# stable_grid_optocoupler.net
KiCad netlist of a schematic drawn in EAGLE
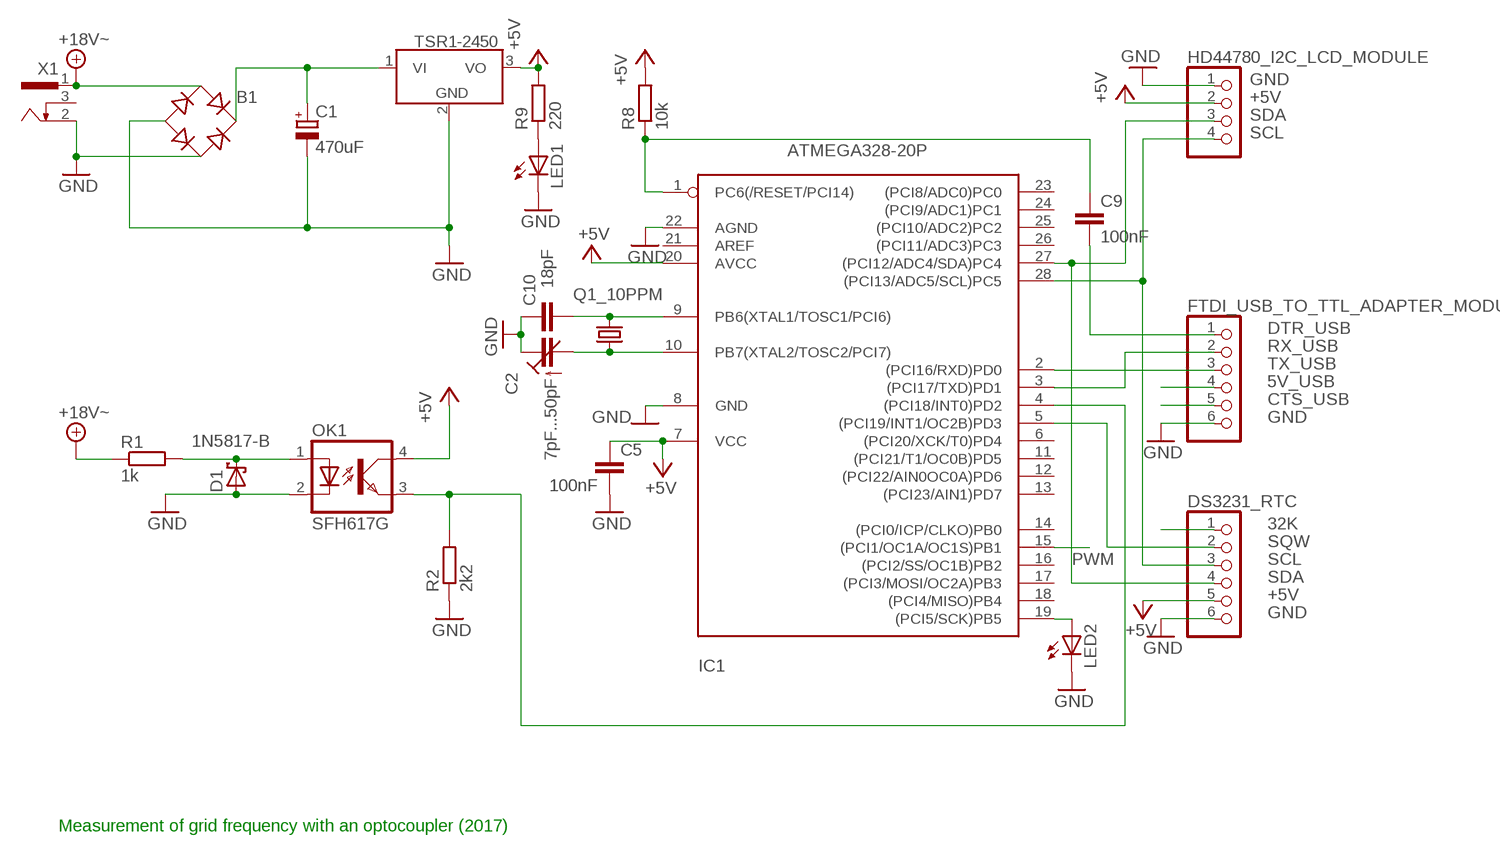
[diagram p0: schematic, sheet 1]

(export (version "E")
  (design (tool "Eeschema 10.0.6"))
  (components
    (comp (ref "B1")
      (value "B-DIL")
      (footprint "eagle-import:B-DIL")
      (libsource (lib "eagle-import") (part "B-DIL"))
    )
    (comp (ref "C1")
      (value "470uF")
      (footprint "eagle-import:085CS_1AR")
      (libsource (lib "eagle-import") (part "CPOL-EU085CS-1AR"))
    )
    (comp (ref "C2")
      (value "7pF...50pF")
      (footprint "eagle-import:CTRIM808-BC")
      (libsource (lib "eagle-import") (part "C-TRIMM808"))
    )
    (comp (ref "C5")
      (value "100nF")
      (footprint "eagle-import:C025-024X044")
      (libsource (lib "eagle-import") (part "C-EU025-024X044"))
    )
    (comp (ref "C9")
      (value "100nF")
      (footprint "eagle-import:C025-024X044")
      (libsource (lib "eagle-import") (part "C-EU025-024X044"))
    )
    (comp (ref "C10")
      (value "18pF")
      (footprint "eagle-import:C025-024X044")
      (libsource (lib "eagle-import") (part "C-EU025-024X044"))
    )
    (comp (ref "D1")
      (value "1N5817-B")
      (footprint "eagle-import:DO41-7.6")
      (libsource (lib "eagle-import") (part "1N5817-B"))
    )
    (comp (ref "DS3231_RTC")
      (value "PINHD-1X6")
      (footprint "eagle-import:1X06")
      (libsource (lib "eagle-import") (part "PINHD-1X6"))
    )
    (comp (ref "FTDI_USB_TO_TTL_ADAPTER_MODULE")
      (value "PINHD-1X6")
      (footprint "eagle-import:1X06")
      (libsource (lib "eagle-import") (part "PINHD-1X6"))
    )
    (comp (ref "HD44780_I2C_LCD_MODULE")
      (value "PINHD-1X4")
      (footprint "eagle-import:1X04")
      (libsource (lib "eagle-import") (part "PINHD-1X4"))
    )
    (comp (ref "IC1")
      (value "ATMEGA328-20P")
      (footprint "eagle-import:DIL28-3")
      (libsource (lib "eagle-import") (part "ATMEGA328P-20"))
    )
    (comp (ref "LED1")
      (value "LAP4-BOTTOM")
      (footprint "eagle-import:P47F-BOTTOM")
      (libsource (lib "eagle-import") (part "P4-BOTTOMLA"))
    )
    (comp (ref "LED2")
      (value "LYP4-BOTTOM")
      (footprint "eagle-import:P47F-BOTTOM")
      (libsource (lib "eagle-import") (part "P4-BOTTOMLY"))
    )
    (comp (ref "OK1")
      (value "SFH617G")
      (footprint "eagle-import:DIL04B")
      (fields (field (name "MF") "VISHAY/TELEFUNKEN") (field (name "MPN") "SFH617A-3"))
      (libsource (lib "eagle-import") (part "SFH617G"))
    )
    (comp (ref "Q1_10PPM")
      (value "CRYSTALHC49S")
      (footprint "eagle-import:HC49_S")
      (libsource (lib "eagle-import") (part "CRYSTALHC49S"))
    )
    (comp (ref "R1")
      (value "1k")
      (footprint "eagle-import:M0805")
      (libsource (lib "eagle-import") (part "R-EU_M0805"))
    )
    (comp (ref "R2")
      (value "2k2")
      (footprint "eagle-import:M0805")
      (libsource (lib "eagle-import") (part "R-EU_M0805"))
    )
    (comp (ref "R8")
      (value "10k")
      (footprint "eagle-import:M0805")
      (libsource (lib "eagle-import") (part "R-EU_M0805"))
    )
    (comp (ref "R9")
      (value "220")
      (footprint "eagle-import:M0805")
      (libsource (lib "eagle-import") (part "R-EU_M0805"))
    )
    (comp (ref "TSR1-2450")
      (value "TSR_1-24_")
      (footprint "eagle-import:TSR-1")
      (libsource (lib "eagle-import") (part "TSR_1-24_"))
    )
    (comp (ref "X1")
      (value "9V")
      (footprint "eagle-import:733980-62")
      (libsource (lib "eagle-import") (part "73398?0-62"))
    )
  )
  (nets
    (net (code "1") (name "+5V") (class "Default")
      (node (ref "C5") (pin "1") (pinfunction "1_1") (pintype "passive"))
      (node (ref "DS3231_RTC") (pin "5") (pinfunction "5_5") (pintype "passive"))
      (node (ref "HD44780_I2C_LCD_MODULE") (pin "2") (pinfunction "2_2") (pintype "passive"))
      (node (ref "IC1") (pin "20") (pinfunction "AVCC_20") (pintype "bidirectional"))
      (node (ref "IC1") (pin "7") (pinfunction "VCC_7") (pintype "bidirectional"))
      (node (ref "OK1") (pin "4") (pinfunction "COL_4") (pintype "passive"))
      (node (ref "R8") (pin "2") (pinfunction "2_2") (pintype "passive"))
      (node (ref "R9") (pin "2") (pinfunction "2_2") (pintype "passive"))
      (node (ref "TSR1-2450") (pin "3") (pinfunction "VO_3") (pintype "power_in"))
    )
    (net (code "2") (name "+18V~") (class "Default")
      (node (ref "B1") (pin "AC1") (pinfunction "AC1_AC1") (pintype "passive"))
      (node (ref "R1") (pin "1") (pinfunction "1_1") (pintype "passive"))
      (node (ref "X1") (pin "1") (pinfunction "1_1") (pintype "passive"))
    )
    (net (code "3") (name "/5V_USB") (class "Default")
      (node (ref "FTDI_USB_TO_TTL_ADAPTER_MODULE") (pin "4") (pinfunction "4_4") (pintype "passive"))
    )
    (net (code "4") (name "/32K") (class "Default")
      (node (ref "DS3231_RTC") (pin "1") (pinfunction "1_1") (pintype "passive"))
    )
    (net (code "5") (name "/CTS_USB") (class "Default")
      (node (ref "FTDI_USB_TO_TTL_ADAPTER_MODULE") (pin "5") (pinfunction "5_5") (pintype "passive"))
    )
    (net (code "6") (name "/DTR_USB") (class "Default")
      (node (ref "C9") (pin "2") (pinfunction "2_2") (pintype "passive"))
      (node (ref "FTDI_USB_TO_TTL_ADAPTER_MODULE") (pin "1") (pinfunction "1_1") (pintype "passive"))
    )
    (net (code "7") (name "/PWM") (class "Default")
      (node (ref "IC1") (pin "15") (pinfunction "(PCI1/OC1A/OC1S)PB1_15") (pintype "bidirectional"))
    )
    (net (code "8") (name "/RX_USB") (class "Default")
      (node (ref "FTDI_USB_TO_TTL_ADAPTER_MODULE") (pin "2") (pinfunction "2_2") (pintype "passive"))
      (node (ref "IC1") (pin "3") (pinfunction "(PCI17/TXD)PD1_3") (pintype "bidirectional"))
    )
    (net (code "9") (name "/SCL") (class "Default")
      (node (ref "DS3231_RTC") (pin "3") (pinfunction "3_3") (pintype "passive"))
      (node (ref "HD44780_I2C_LCD_MODULE") (pin "4") (pinfunction "4_4") (pintype "passive"))
      (node (ref "IC1") (pin "28") (pinfunction "(PCI13/ADC5/SCL)PC5_28") (pintype "bidirectional"))
    )
    (net (code "10") (name "/SDA") (class "Default")
      (node (ref "DS3231_RTC") (pin "4") (pinfunction "4_4") (pintype "passive"))
      (node (ref "HD44780_I2C_LCD_MODULE") (pin "3") (pinfunction "3_3") (pintype "passive"))
      (node (ref "IC1") (pin "27") (pinfunction "(PCI12/ADC4/SDA)PC4_27") (pintype "bidirectional"))
    )
    (net (code "11") (name "/SQW") (class "Default")
      (node (ref "DS3231_RTC") (pin "2") (pinfunction "2_2") (pintype "passive"))
      (node (ref "IC1") (pin "5") (pinfunction "(PCI19/INT1/OC2B)PD3_5") (pintype "bidirectional"))
    )
    (net (code "12") (name "/TX_USB") (class "Default")
      (node (ref "FTDI_USB_TO_TTL_ADAPTER_MODULE") (pin "3") (pinfunction "3_3") (pintype "passive"))
      (node (ref "IC1") (pin "2") (pinfunction "(PCI16/RXD)PD0_2") (pintype "bidirectional"))
    )
    (net (code "13") (name "GND") (class "Default")
      (node (ref "B1") (pin "-") (pinfunction "-_-") (pintype "passive"))
      (node (ref "B1") (pin "AC2") (pinfunction "AC2_AC2") (pintype "passive"))
      (node (ref "C1") (pin "-") (pinfunction "-_-") (pintype "passive"))
      (node (ref "C10") (pin "1") (pinfunction "1_1") (pintype "passive"))
      (node (ref "C2") (pin "1") (pinfunction "E_1") (pintype "passive"))
      (node (ref "C5") (pin "2") (pinfunction "2_2") (pintype "passive"))
      (node (ref "D1") (pin "A") (pinfunction "A_A") (pintype "passive"))
      (node (ref "DS3231_RTC") (pin "6") (pinfunction "6_6") (pintype "passive"))
      (node (ref "FTDI_USB_TO_TTL_ADAPTER_MODULE") (pin "6") (pinfunction "6_6") (pintype "passive"))
      (node (ref "HD44780_I2C_LCD_MODULE") (pin "1") (pinfunction "1_1") (pintype "passive"))
      (node (ref "IC1") (pin "22") (pinfunction "AGND_22") (pintype "bidirectional"))
      (node (ref "IC1") (pin "8") (pinfunction "GND_8") (pintype "bidirectional"))
      (node (ref "LED1") (pin "C") (pinfunction "C_C") (pintype "passive"))
      (node (ref "LED2") (pin "C") (pinfunction "C_C") (pintype "passive"))
      (node (ref "OK1") (pin "2") (pinfunction "C_2") (pintype "passive"))
      (node (ref "R2") (pin "1") (pinfunction "1_1") (pintype "passive"))
      (node (ref "TSR1-2450") (pin "2") (pinfunction "GND_2") (pintype "power_in"))
      (node (ref "X1") (pin "2") (pinfunction "2_2") (pintype "passive"))
    )
    (net (code "14") (name "Net-(C2-A)") (class "Default")
      (node (ref "C2") (pin "2") (pinfunction "A_2") (pintype "passive"))
      (node (ref "IC1") (pin "10") (pinfunction "PB7(XTAL2/TOSC2/PCI7)_10") (pintype "bidirectional"))
      (node (ref "Q1_10PPM") (pin "1") (pinfunction "1_1") (pintype "passive"))
    )
    (net (code "15") (name "Net-(IC1-(PCI5{slash}SCK)PB5)") (class "Default")
      (node (ref "IC1") (pin "19") (pinfunction "(PCI5/SCK)PB5_19") (pintype "bidirectional"))
      (node (ref "LED2") (pin "A") (pinfunction "A_A") (pintype "passive"))
    )
    (net (code "16") (name "Net-(IC1-(PCI18{slash}INT0)PD2)") (class "Default")
      (node (ref "IC1") (pin "4") (pinfunction "(PCI18/INT0)PD2_4") (pintype "bidirectional"))
      (node (ref "OK1") (pin "3") (pinfunction "EMIT_3") (pintype "passive"))
      (node (ref "R2") (pin "2") (pinfunction "2_2") (pintype "passive"))
    )
    (net (code "17") (name "Net-(IC1-PB6(XTAL1{slash}TOSC1{slash}PCI6))") (class "Default")
      (node (ref "C10") (pin "2") (pinfunction "2_2") (pintype "passive"))
      (node (ref "IC1") (pin "9") (pinfunction "PB6(XTAL1/TOSC1/PCI6)_9") (pintype "bidirectional"))
      (node (ref "Q1_10PPM") (pin "2") (pinfunction "2_2") (pintype "passive"))
    )
    (net (code "18") (name "Net-(IC1-PC6({slash}RESET{slash}PCI14))") (class "Default")
      (node (ref "C9") (pin "1") (pinfunction "1_1") (pintype "passive"))
      (node (ref "IC1") (pin "1") (pinfunction "PC6(/RESET/PCI14)_1") (pintype "bidirectional"))
      (node (ref "R8") (pin "1") (pinfunction "1_1") (pintype "passive"))
    )
    (net (code "19") (name "Net-(LED1-PadA)") (class "Default")
      (node (ref "LED1") (pin "A") (pinfunction "A_A") (pintype "passive"))
      (node (ref "R9") (pin "1") (pinfunction "1_1") (pintype "passive"))
    )
    (net (code "20") (name "Net-(OK1-A)") (class "Default")
      (node (ref "D1") (pin "C") (pinfunction "C_C") (pintype "passive"))
      (node (ref "OK1") (pin "1") (pinfunction "A_1") (pintype "passive"))
      (node (ref "R1") (pin "2") (pinfunction "2_2") (pintype "passive"))
    )
    (net (code "21") (name "Net-(TSR1-2450-VI)") (class "Default")
      (node (ref "B1") (pin "+") (pinfunction "+_+") (pintype "passive"))
      (node (ref "C1") (pin "+") (pinfunction "+_+") (pintype "passive"))
      (node (ref "TSR1-2450") (pin "1") (pinfunction "VI_1") (pintype "power_in"))
    )
    (net (code "22") (name "unconnected-(IC1-(PCI0{slash}ICP{slash}CLKO)PB0-Pad14)") (class "Default")
      (node (ref "IC1") (pin "14") (pinfunction "(PCI0/ICP/CLKO)PB0_14") (pintype "bidirectional"))
    )
    (net (code "23") (name "unconnected-(IC1-(PCI2{slash}SS{slash}OC1B)PB2-Pad16)") (class "Default")
      (node (ref "IC1") (pin "16") (pinfunction "(PCI2/SS/OC1B)PB2_16") (pintype "bidirectional"))
    )
    (net (code "24") (name "unconnected-(IC1-(PCI3{slash}MOSI{slash}OC2A)PB3-Pad17)") (class "Default")
      (node (ref "IC1") (pin "17") (pinfunction "(PCI3/MOSI/OC2A)PB3_17") (pintype "bidirectional"))
    )
    (net (code "25") (name "unconnected-(IC1-(PCI4{slash}MISO)PB4-Pad18)") (class "Default")
      (node (ref "IC1") (pin "18") (pinfunction "(PCI4/MISO)PB4_18") (pintype "bidirectional"))
    )
    (net (code "26") (name "unconnected-(IC1-(PCI8{slash}ADC0)PC0-Pad23)") (class "Default")
      (node (ref "IC1") (pin "23") (pinfunction "(PCI8/ADC0)PC0_23") (pintype "bidirectional"))
    )
    (net (code "27") (name "unconnected-(IC1-(PCI9{slash}ADC1)PC1-Pad24)") (class "Default")
      (node (ref "IC1") (pin "24") (pinfunction "(PCI9/ADC1)PC1_24") (pintype "bidirectional"))
    )
    (net (code "28") (name "unconnected-(IC1-(PCI10{slash}ADC2)PC2-Pad25)") (class "Default")
      (node (ref "IC1") (pin "25") (pinfunction "(PCI10/ADC2)PC2_25") (pintype "bidirectional"))
    )
    (net (code "29") (name "unconnected-(IC1-(PCI11{slash}ADC3)PC3-Pad26)") (class "Default")
      (node (ref "IC1") (pin "26") (pinfunction "(PCI11/ADC3)PC3_26") (pintype "bidirectional"))
    )
    (net (code "30") (name "unconnected-(IC1-(PCI20{slash}XCK{slash}T0)PD4-Pad6)") (class "Default")
      (node (ref "IC1") (pin "6") (pinfunction "(PCI20/XCK/T0)PD4_6") (pintype "bidirectional"))
    )
    (net (code "31") (name "unconnected-(IC1-(PCI21{slash}T1{slash}OC0B)PD5-Pad11)") (class "Default")
      (node (ref "IC1") (pin "11") (pinfunction "(PCI21/T1/OC0B)PD5_11") (pintype "bidirectional"))
    )
    (net (code "32") (name "unconnected-(IC1-(PCI22{slash}AIN0OC0A)PD6-Pad12)") (class "Default")
      (node (ref "IC1") (pin "12") (pinfunction "(PCI22/AIN0OC0A)PD6_12") (pintype "bidirectional"))
    )
    (net (code "33") (name "unconnected-(IC1-(PCI23{slash}AIN1)PD7-Pad13)") (class "Default")
      (node (ref "IC1") (pin "13") (pinfunction "(PCI23/AIN1)PD7_13") (pintype "bidirectional"))
    )
    (net (code "34") (name "unconnected-(IC1-AREF-Pad21)") (class "Default")
      (node (ref "IC1") (pin "21") (pinfunction "AREF_21") (pintype "bidirectional"))
    )
    (net (code "35") (name "unconnected-(X1-Pad3)") (class "Default")
      (node (ref "X1") (pin "3") (pinfunction "3_3") (pintype "passive"))
    )
  )
)
